# peripheral.net
KiCad netlist of a schematic drawn in EAGLE
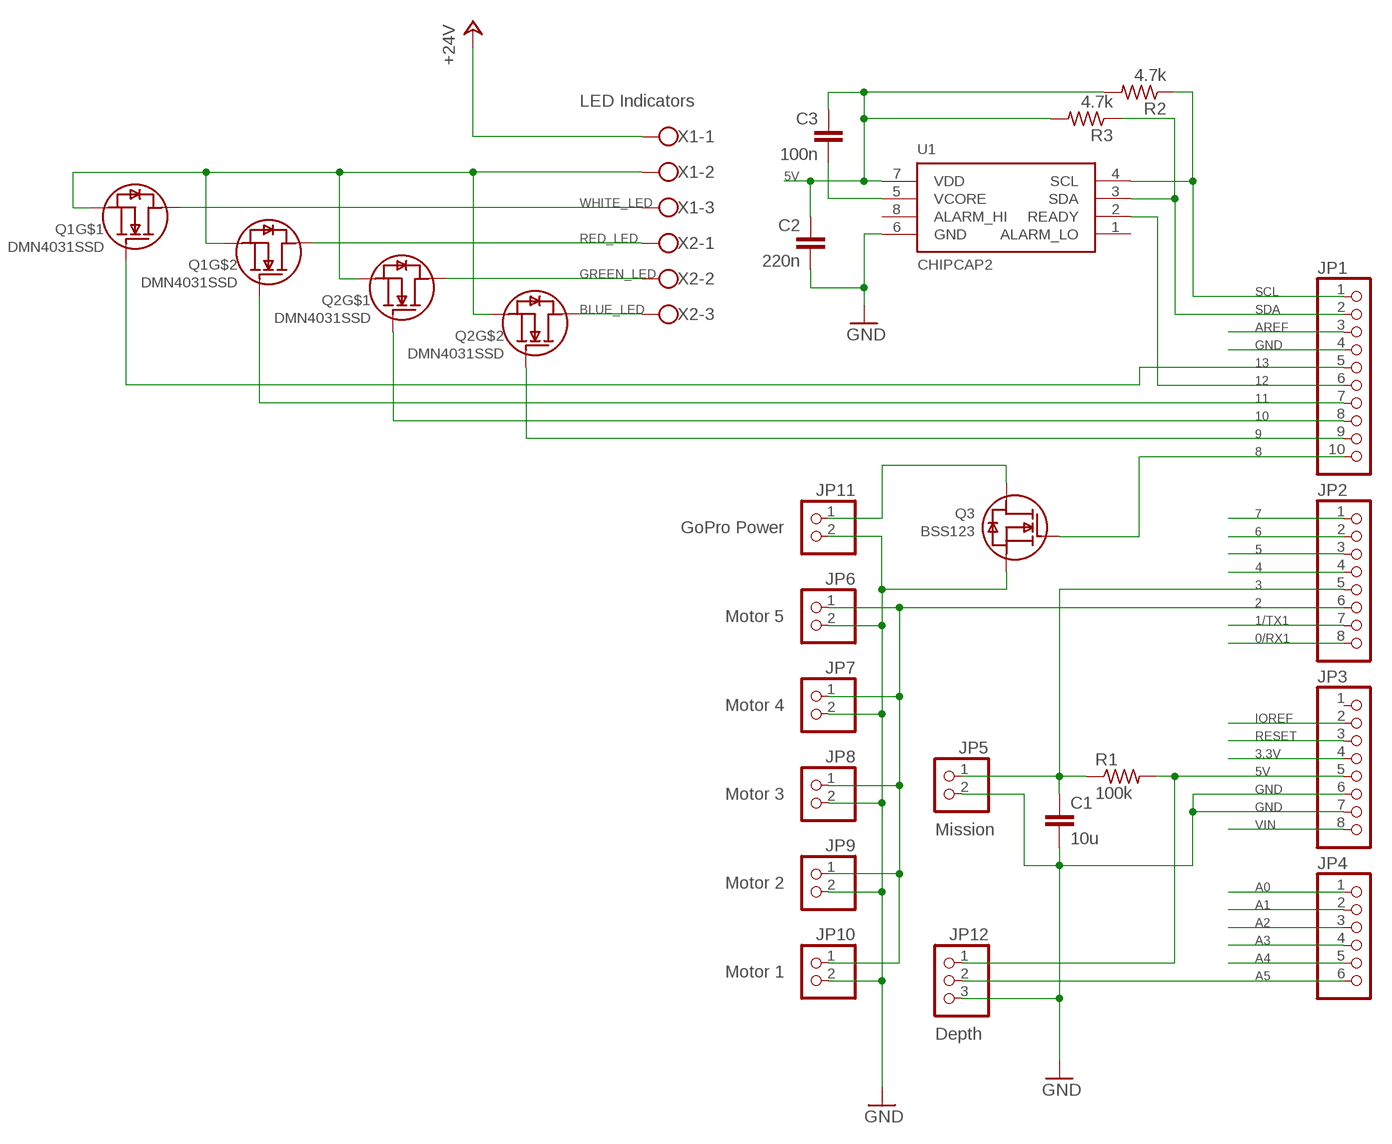
[diagram p0: schematic, sheet 1]

(export (version "E")
  (design (tool "Eeschema 10.0.6"))
  (components
    (comp (ref "C1")
      (value "10u")
      (footprint "eagle-import:C0805K")
      (libsource (lib "eagle-import") (part "C-EUC0805K"))
    )
    (comp (ref "C2")
      (value "220n")
      (footprint "eagle-import:C0603")
      (libsource (lib "eagle-import") (part "C-EUC0603"))
    )
    (comp (ref "C3")
      (value "100n")
      (footprint "eagle-import:C0603")
      (libsource (lib "eagle-import") (part "C-EUC0603"))
    )
    (comp (ref "JP1")
      (value "PINHD-1X10")
      (footprint "eagle-import:1X10")
      (libsource (lib "eagle-import") (part "PINHD-1X10"))
    )
    (comp (ref "JP2")
      (value "PINHD-1X8")
      (footprint "eagle-import:1X08")
      (libsource (lib "eagle-import") (part "PINHD-1X8"))
    )
    (comp (ref "JP3")
      (value "PINHD-1X8")
      (footprint "eagle-import:1X08")
      (libsource (lib "eagle-import") (part "PINHD-1X8"))
    )
    (comp (ref "JP4")
      (value "PINHD-1X6")
      (footprint "eagle-import:1X06")
      (libsource (lib "eagle-import") (part "PINHD-1X6"))
    )
    (comp (ref "JP5")
      (value "PINHD-1X2")
      (footprint "eagle-import:1X02")
      (libsource (lib "eagle-import") (part "PINHD-1X2"))
    )
    (comp (ref "JP6")
      (value "PINHD-1X2")
      (footprint "eagle-import:1X02")
      (libsource (lib "eagle-import") (part "PINHD-1X2"))
    )
    (comp (ref "JP7")
      (value "PINHD-1X2")
      (footprint "eagle-import:1X02")
      (libsource (lib "eagle-import") (part "PINHD-1X2"))
    )
    (comp (ref "JP8")
      (value "PINHD-1X2")
      (footprint "eagle-import:1X02")
      (libsource (lib "eagle-import") (part "PINHD-1X2"))
    )
    (comp (ref "JP9")
      (value "PINHD-1X2")
      (footprint "eagle-import:1X02")
      (libsource (lib "eagle-import") (part "PINHD-1X2"))
    )
    (comp (ref "JP10")
      (value "PINHD-1X2")
      (footprint "eagle-import:1X02")
      (libsource (lib "eagle-import") (part "PINHD-1X2"))
    )
    (comp (ref "JP11")
      (value "PINHD-1X2")
      (footprint "eagle-import:1X02")
      (libsource (lib "eagle-import") (part "PINHD-1X2"))
    )
    (comp (ref "JP12")
      (value "PINHD-1X3")
      (footprint "eagle-import:1X03")
      (libsource (lib "eagle-import") (part "PINHD-1X3"))
    )
    (comp (ref "Q1")
      (value "DMN4031SSD")
      (footprint "eagle-import:SO-8")
      (libsource (lib "eagle-import") (part "DMN4031SSD"))
    )
    (comp (ref "Q2")
      (value "DMN4031SSD")
      (footprint "eagle-import:SO-8")
      (libsource (lib "eagle-import") (part "DMN4031SSD"))
    )
    (comp (ref "Q3")
      (value "BSS123")
      (footprint "eagle-import:SOT-23")
      (libsource (lib "eagle-import") (part "BSS123"))
    )
    (comp (ref "R1")
      (value "100k")
      (footprint "eagle-import:R0805")
      (libsource (lib "eagle-import") (part "R-US_R0805"))
    )
    (comp (ref "R2")
      (value "4.7k")
      (footprint "eagle-import:R0603")
      (libsource (lib "eagle-import") (part "R-US_R0603"))
    )
    (comp (ref "R3")
      (value "4.7k")
      (footprint "eagle-import:R0603")
      (libsource (lib "eagle-import") (part "R-US_R0603"))
    )
    (comp (ref "U1")
      (value "CHIPCAP2")
      (footprint "eagle-import:CHIPCAP2")
      (libsource (lib "eagle-import") (part "CHIPCAP2"))
    )
    (comp (ref "X1")
      (value "W237-103")
      (footprint "eagle-import:W237-103")
      (fields (field (name "MPN") "237-103"))
      (libsource (lib "eagle-import") (part "W237-103"))
    )
    (comp (ref "X2")
      (value "W237-103")
      (footprint "eagle-import:W237-103")
      (fields (field (name "MPN") "237-103"))
      (libsource (lib "eagle-import") (part "W237-103"))
    )
  )
  (nets
    (net (code "1") (name "+24V") (class "Default")
      (node (ref "X1") (pin "1") (pinfunction "KL_1") (pintype "passive"))
    )
    (net (code "2") (name "/0{slash}RX1") (class "Default")
      (node (ref "JP2") (pin "8") (pinfunction "8_8") (pintype "passive"))
    )
    (net (code "3") (name "/1{slash}TX1") (class "Default")
      (node (ref "JP2") (pin "7") (pinfunction "7_7") (pintype "passive"))
    )
    (net (code "4") (name "/2") (class "Default")
      (node (ref "JP10") (pin "1") (pinfunction "1_1") (pintype "passive"))
      (node (ref "JP2") (pin "6") (pinfunction "6_6") (pintype "passive"))
      (node (ref "JP6") (pin "1") (pinfunction "1_1") (pintype "passive"))
      (node (ref "JP7") (pin "1") (pinfunction "1_1") (pintype "passive"))
      (node (ref "JP8") (pin "1") (pinfunction "1_1") (pintype "passive"))
      (node (ref "JP9") (pin "1") (pinfunction "1_1") (pintype "passive"))
    )
    (net (code "5") (name "/3") (class "Default")
      (node (ref "C1") (pin "1") (pinfunction "1_1") (pintype "passive"))
      (node (ref "JP2") (pin "5") (pinfunction "5_5") (pintype "passive"))
      (node (ref "JP5") (pin "1") (pinfunction "1_1") (pintype "passive"))
      (node (ref "R1") (pin "1") (pinfunction "1_1") (pintype "passive"))
    )
    (net (code "6") (name "/3.3V") (class "Default")
      (node (ref "JP3") (pin "4") (pinfunction "4_4") (pintype "passive"))
    )
    (net (code "7") (name "/4") (class "Default")
      (node (ref "JP2") (pin "4") (pinfunction "4_4") (pintype "passive"))
    )
    (net (code "8") (name "/5") (class "Default")
      (node (ref "JP2") (pin "3") (pinfunction "3_3") (pintype "passive"))
    )
    (net (code "9") (name "/5V") (class "Default")
      (node (ref "C2") (pin "1") (pinfunction "1_1") (pintype "passive"))
      (node (ref "C3") (pin "1") (pinfunction "1_1") (pintype "passive"))
      (node (ref "JP12") (pin "1") (pinfunction "1_1") (pintype "passive"))
      (node (ref "JP3") (pin "5") (pinfunction "5_5") (pintype "passive"))
      (node (ref "R1") (pin "2") (pinfunction "2_2") (pintype "passive"))
      (node (ref "R2") (pin "2") (pinfunction "2_2") (pintype "passive"))
      (node (ref "R3") (pin "2") (pinfunction "2_2") (pintype "passive"))
      (node (ref "U1") (pin "7") (pinfunction "VDD_7") (pintype "bidirectional"))
    )
    (net (code "10") (name "/6") (class "Default")
      (node (ref "JP2") (pin "2") (pinfunction "2_2") (pintype "passive"))
    )
    (net (code "11") (name "/7") (class "Default")
      (node (ref "JP2") (pin "1") (pinfunction "1_1") (pintype "passive"))
    )
    (net (code "12") (name "/8") (class "Default")
      (node (ref "JP1") (pin "10") (pinfunction "10_10") (pintype "passive"))
      (node (ref "Q3") (pin "1") (pinfunction "G_1") (pintype "bidirectional"))
    )
    (net (code "13") (name "/9") (class "Default")
      (node (ref "JP1") (pin "9") (pinfunction "9_9") (pintype "passive"))
      (node (ref "Q2") (pin "2") (pinfunction "G_2") (pintype "bidirectional"))
    )
    (net (code "14") (name "/10") (class "Default")
      (node (ref "JP1") (pin "8") (pinfunction "8_8") (pintype "passive"))
      (node (ref "Q2") (pin "4") (pinfunction "G_4") (pintype "bidirectional"))
    )
    (net (code "15") (name "/11") (class "Default")
      (node (ref "JP1") (pin "7") (pinfunction "7_7") (pintype "passive"))
      (node (ref "Q1") (pin "2") (pinfunction "G_2") (pintype "bidirectional"))
    )
    (net (code "16") (name "/12") (class "Default")
      (node (ref "JP1") (pin "6") (pinfunction "6_6") (pintype "passive"))
      (node (ref "U1") (pin "2") (pinfunction "READY_2") (pintype "bidirectional"))
    )
    (net (code "17") (name "/13") (class "Default")
      (node (ref "JP1") (pin "5") (pinfunction "5_5") (pintype "passive"))
      (node (ref "Q1") (pin "4") (pinfunction "G_4") (pintype "bidirectional"))
    )
    (net (code "18") (name "/A0") (class "Default")
      (node (ref "JP4") (pin "1") (pinfunction "1_1") (pintype "passive"))
    )
    (net (code "19") (name "/A1") (class "Default")
      (node (ref "JP4") (pin "2") (pinfunction "2_2") (pintype "passive"))
    )
    (net (code "20") (name "/A2") (class "Default")
      (node (ref "JP4") (pin "3") (pinfunction "3_3") (pintype "passive"))
    )
    (net (code "21") (name "/A3") (class "Default")
      (node (ref "JP4") (pin "4") (pinfunction "4_4") (pintype "passive"))
    )
    (net (code "22") (name "/A4") (class "Default")
      (node (ref "JP4") (pin "5") (pinfunction "5_5") (pintype "passive"))
    )
    (net (code "23") (name "/A5") (class "Default")
      (node (ref "JP12") (pin "2") (pinfunction "2_2") (pintype "passive"))
      (node (ref "JP4") (pin "6") (pinfunction "6_6") (pintype "passive"))
    )
    (net (code "24") (name "/AREF") (class "Default")
      (node (ref "JP1") (pin "3") (pinfunction "3_3") (pintype "passive"))
    )
    (net (code "25") (name "/BLUE_LED") (class "Default")
      (node (ref "Q2") (pin "7") (pinfunction "D_7") (pintype "bidirectional"))
      (node (ref "Q2") (pin "8") (pinfunction "D_8") (pintype "bidirectional"))
      (node (ref "X2") (pin "3") (pinfunction "KL_3") (pintype "passive"))
    )
    (net (code "26") (name "/GREEN_LED") (class "Default")
      (node (ref "Q2") (pin "5") (pinfunction "D_5") (pintype "bidirectional"))
      (node (ref "Q2") (pin "6") (pinfunction "D_6") (pintype "bidirectional"))
      (node (ref "X2") (pin "2") (pinfunction "KL_2") (pintype "passive"))
    )
    (net (code "27") (name "/IOREF") (class "Default")
      (node (ref "JP3") (pin "2") (pinfunction "2_2") (pintype "passive"))
    )
    (net (code "28") (name "/RED_LED") (class "Default")
      (node (ref "Q1") (pin "7") (pinfunction "D_7") (pintype "bidirectional"))
      (node (ref "Q1") (pin "8") (pinfunction "D_8") (pintype "bidirectional"))
      (node (ref "X2") (pin "1") (pinfunction "KL_1") (pintype "passive"))
    )
    (net (code "29") (name "/RESET") (class "Default")
      (node (ref "JP3") (pin "3") (pinfunction "3_3") (pintype "passive"))
    )
    (net (code "30") (name "/SCL") (class "Default")
      (node (ref "JP1") (pin "1") (pinfunction "1_1") (pintype "passive"))
      (node (ref "R2") (pin "1") (pinfunction "1_1") (pintype "passive"))
      (node (ref "U1") (pin "4") (pinfunction "SCL_4") (pintype "bidirectional"))
    )
    (net (code "31") (name "/SDA") (class "Default")
      (node (ref "JP1") (pin "2") (pinfunction "2_2") (pintype "passive"))
      (node (ref "R3") (pin "1") (pinfunction "1_1") (pintype "passive"))
      (node (ref "U1") (pin "3") (pinfunction "SDA_3") (pintype "bidirectional"))
    )
    (net (code "32") (name "/VIN") (class "Default")
      (node (ref "JP3") (pin "8") (pinfunction "8_8") (pintype "passive"))
    )
    (net (code "33") (name "/WHITE_LED") (class "Default")
      (node (ref "Q1") (pin "5") (pinfunction "D_5") (pintype "bidirectional"))
      (node (ref "Q1") (pin "6") (pinfunction "D_6") (pintype "bidirectional"))
      (node (ref "X1") (pin "3") (pinfunction "KL_3") (pintype "passive"))
    )
    (net (code "34") (name "GND") (class "Default")
      (node (ref "C1") (pin "2") (pinfunction "2_2") (pintype "passive"))
      (node (ref "C2") (pin "2") (pinfunction "2_2") (pintype "passive"))
      (node (ref "JP1") (pin "4") (pinfunction "4_4") (pintype "passive"))
      (node (ref "JP10") (pin "2") (pinfunction "2_2") (pintype "passive"))
      (node (ref "JP11") (pin "2") (pinfunction "2_2") (pintype "passive"))
      (node (ref "JP12") (pin "3") (pinfunction "3_3") (pintype "passive"))
      (node (ref "JP3") (pin "6") (pinfunction "6_6") (pintype "passive"))
      (node (ref "JP3") (pin "7") (pinfunction "7_7") (pintype "passive"))
      (node (ref "JP5") (pin "2") (pinfunction "2_2") (pintype "passive"))
      (node (ref "JP6") (pin "2") (pinfunction "2_2") (pintype "passive"))
      (node (ref "JP7") (pin "2") (pinfunction "2_2") (pintype "passive"))
      (node (ref "JP8") (pin "2") (pinfunction "2_2") (pintype "passive"))
      (node (ref "JP9") (pin "2") (pinfunction "2_2") (pintype "passive"))
      (node (ref "Q3") (pin "3") (pinfunction "S_3") (pintype "bidirectional"))
      (node (ref "U1") (pin "6") (pinfunction "GND_6") (pintype "bidirectional"))
    )
    (net (code "35") (name "Net-(Q1A-S)") (class "Default")
      (node (ref "Q1") (pin "1") (pinfunction "S_1") (pintype "bidirectional"))
      (node (ref "Q1") (pin "3") (pinfunction "S_3") (pintype "bidirectional"))
      (node (ref "Q2") (pin "1") (pinfunction "S_1") (pintype "bidirectional"))
      (node (ref "Q2") (pin "3") (pinfunction "S_3") (pintype "bidirectional"))
      (node (ref "X1") (pin "2") (pinfunction "KL_2") (pintype "passive"))
    )
    (net (code "36") (name "Net-(Q3-D)") (class "Default")
      (node (ref "JP11") (pin "1") (pinfunction "1_1") (pintype "passive"))
      (node (ref "Q3") (pin "2") (pinfunction "D_2") (pintype "bidirectional"))
    )
    (net (code "37") (name "Net-(U1-VCORE)") (class "Default")
      (node (ref "C3") (pin "2") (pinfunction "2_2") (pintype "passive"))
      (node (ref "U1") (pin "5") (pinfunction "VCORE_5") (pintype "bidirectional"))
    )
    (net (code "38") (name "unconnected-(JP3-Pad1)") (class "Default")
      (node (ref "JP3") (pin "1") (pinfunction "1_1") (pintype "passive"))
    )
    (net (code "39") (name "unconnected-(U1-ALARM_HI-Pad8)") (class "Default")
      (node (ref "U1") (pin "8") (pinfunction "ALARM_HI_8") (pintype "bidirectional"))
    )
    (net (code "40") (name "unconnected-(U1-ALARM_LO-Pad1)") (class "Default")
      (node (ref "U1") (pin "1") (pinfunction "ALARM_LO_1") (pintype "bidirectional"))
    )
  )
)
